# SCH_ESP32-v3_28-11-2025_2025-11-29.net
KiCad netlist of a schematic drawn in EasyEDA
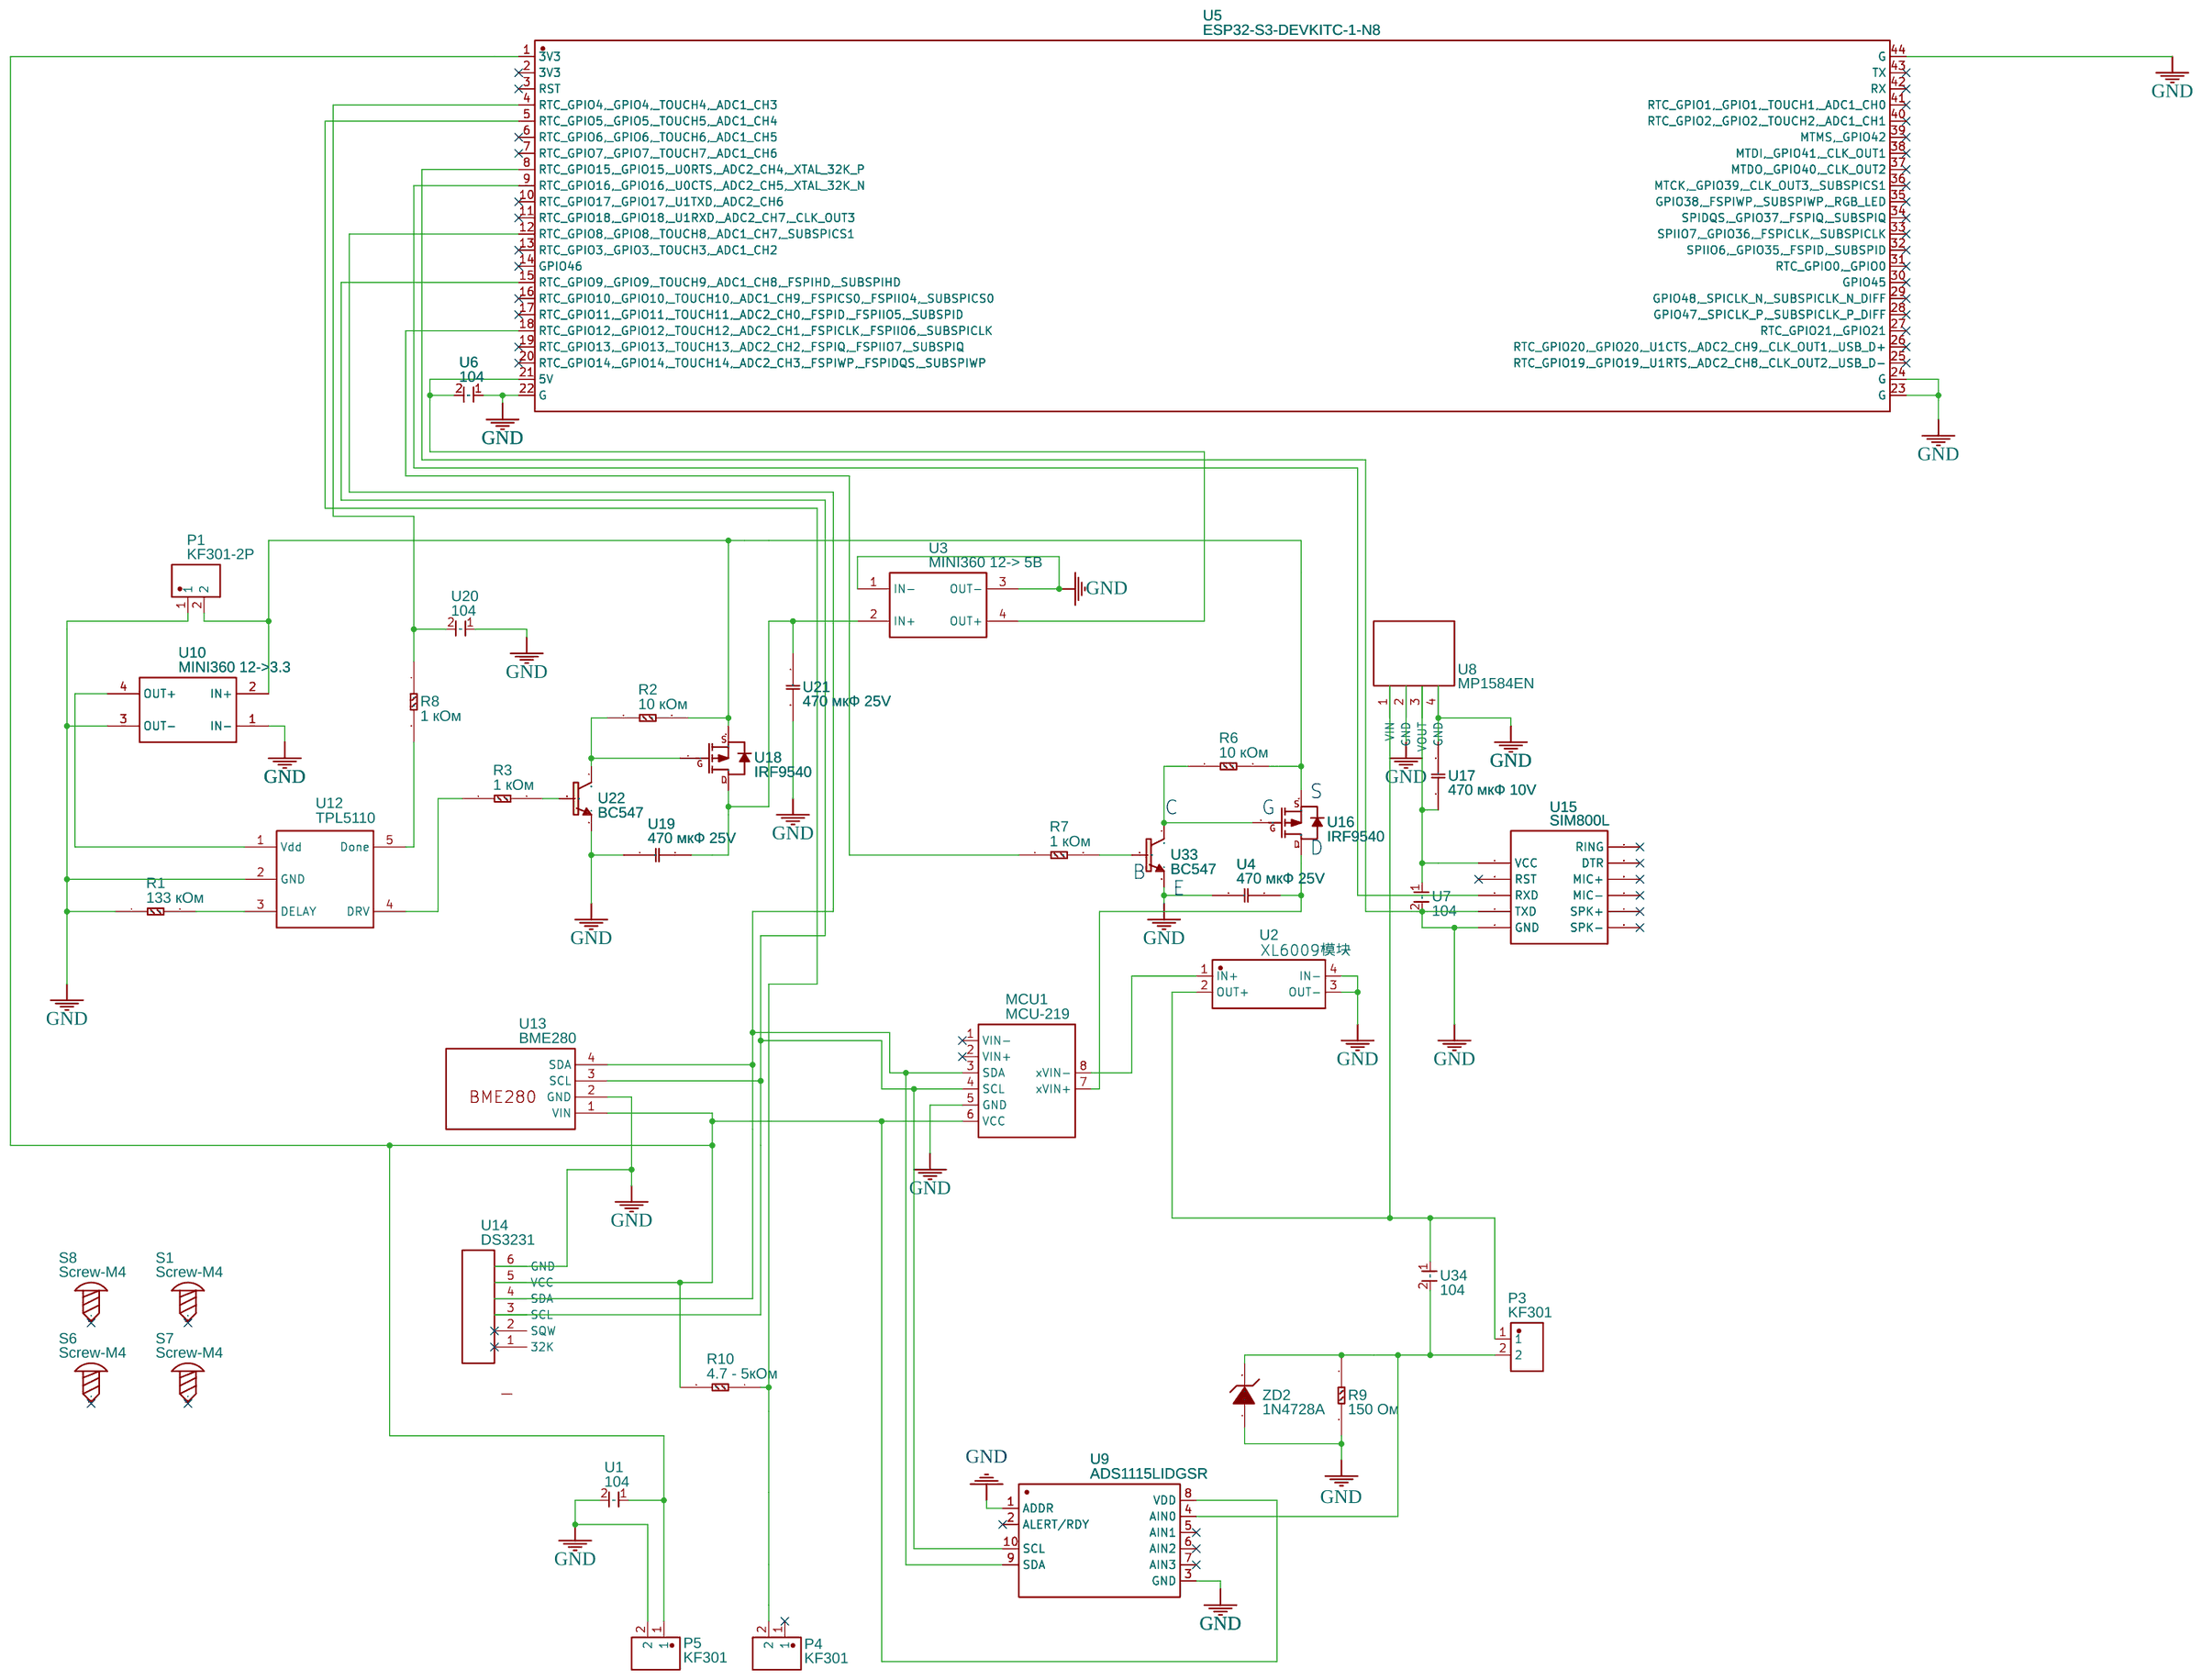
[diagram p0: schematic sheet]

(export (version "E")
  (design (tool "Eeschema 10.0.6"))
  (components
    (comp (ref "MCU1") (value "MCU-219") (libsource (lib "") (part "MCU-219")))
    (comp (ref "P1")
      (value "KF301-2P")
      (fields (field (name "Manufacturer Part") "KF301-2P接线端子"))
      (libsource (lib "") (part "KF301-2P VCC Y GND"))
    )
    (comp (ref "P3")
      (value "KF301")
      (fields (field (name "Manufacturer Part") "KF301-2P接线端子"))
      (libsource (lib "") (part "KF301-2P VCC Y GND_2"))
    )
    (comp (ref "P4")
      (value "KF301")
      (fields (field (name "Manufacturer Part") "KF301-2P接线端子"))
      (libsource (lib "") (part "KF301-2P VCC Y GND_1"))
    )
    (comp (ref "P5")
      (value "KF301")
      (fields (field (name "Manufacturer Part") "KF301-2P接线端子"))
      (libsource (lib "") (part "KF301-2P VCC Y GND_1"))
    )
    (comp (ref "R1") (value "133 кОм") (libsource (lib "") (part "R_")))
    (comp (ref "R2") (value "10 кОм") (libsource (lib "") (part "R_")))
    (comp (ref "R3") (value "1 кОм") (libsource (lib "") (part "R_")))
    (comp (ref "R6") (value "10 кОм") (libsource (lib "") (part "R_")))
    (comp (ref "R7") (value "1 кОм") (libsource (lib "") (part "R_")))
    (comp (ref "R8") (value "1 кОм") (libsource (lib "") (part "R__2")))
    (comp (ref "R9") (value "150 Ом") (libsource (lib "") (part "R__2")))
    (comp (ref "R10") (value "4.7 - 5кОм") (libsource (lib "") (part "R__1")))
    (comp (ref "S1") (value "Screw-M4") (libsource (lib "") (part "Screw-M4")))
    (comp (ref "S6") (value "Screw-M4") (libsource (lib "") (part "Screw-M4")))
    (comp (ref "S7") (value "Screw-M4") (libsource (lib "") (part "Screw-M4")))
    (comp (ref "S8") (value "Screw-M4") (libsource (lib "") (part "Screw-M4")))
    (comp (ref "U1")
      (value "104")
      (fields (field (name "Manufacturer") "Fe"))
      (libsource (lib "") (part "104"))
    )
    (comp (ref "U2")
      (value "XL6009模块")
      (fields (field (name "Manufacturer Part") "xl6009模块"))
      (libsource (lib "") (part "XL6009模块"))
    )
    (comp (ref "U3")
      (value "MINI360 12-> 5В")
      (fields (field (name "Manufacturer Part") "Mini360"))
      (libsource (lib "") (part "MINI360BUCK"))
    )
    (comp (ref "U4") (value "470 мкФ 25V") (libsource (lib "") (part "C__1")))
    (comp (ref "U5")
      (value "ESP32-S3-DEVKITC-1-N8")
      (fields (field (name "Manufacturer") "ESPRESSIF(乐鑫)"))
      (libsource (lib "") (part "ESP32-S3-DEVKITC-1-N8"))
    )
    (comp (ref "U6")
      (value "104")
      (fields (field (name "Manufacturer") "Fe"))
      (libsource (lib "") (part "104"))
    )
    (comp (ref "U7")
      (value "104")
      (fields (field (name "Manufacturer") "Fe"))
      (libsource (lib "") (part "104_1"))
    )
    (comp (ref "U8") (value "MP1584EN") (libsource (lib "") (part "MP1584EN")))
    (comp (ref "U9")
      (value "ADS1115LIDGSR")
      (fields (field (name "Manufacturer") "TI(德州仪器)"))
      (libsource (lib "") (part "ADS1115LIDGSR"))
    )
    (comp (ref "U10")
      (value "MINI360 12->3.3")
      (fields (field (name "Manufacturer Part") "Mini360"))
      (libsource (lib "") (part "MINI360BUCK_1"))
    )
    (comp (ref "U12")
      (value "TPL5110")
      (fields (field (name "Manufacturer Part") "3435"))
      (libsource (lib "") (part "ADAFRUIT TPL5110 BREAKOUT"))
    )
    (comp (ref "U13") (value "BME280") (libsource (lib "") (part "BME280")))
    (comp (ref "U14") (value "DS3231") (libsource (lib "") (part "DS3231 upright")))
    (comp (ref "U15") (value "SIM800L") (libsource (lib "") (part "SIM800L")))
    (comp (ref "U16") (value "IRF9540") (libsource (lib "") (part "IRF9540")))
    (comp (ref "U17") (value "470 мкФ 10V") (libsource (lib "") (part "C_")))
    (comp (ref "U18") (value "IRF9540") (libsource (lib "") (part "IRF9540")))
    (comp (ref "U19") (value "470 мкФ 25V") (libsource (lib "") (part "C__1")))
    (comp (ref "U20")
      (value "104")
      (fields (field (name "Manufacturer") "Fe"))
      (libsource (lib "") (part "104"))
    )
    (comp (ref "U21") (value "470 мкФ 25V") (libsource (lib "") (part "C_")))
    (comp (ref "U22") (value "BC547") (libsource (lib "") (part "BC547")))
    (comp (ref "U33") (value "BC547") (libsource (lib "") (part "BC547")))
    (comp (ref "U34")
      (value "104")
      (fields (field (name "Manufacturer") "Fe"))
      (libsource (lib "") (part "104_1"))
    )
    (comp (ref "ZD2")
      (value "1N4728A")
      (fields (field (name "Manufacturer") "ST(先科)"))
      (libsource (lib "") (part "1N4728A"))
    )
  )
  (nets
    (net (code "1") (name "GND") (class "Default")
      (node (ref "MCU1") (pin "5") (pinfunction "GND_5") (pintype "unspecified"))
      (node (ref "P1") (pin "1") (pinfunction "1_1") (pintype "unspecified"))
      (node (ref "P5") (pin "2") (pinfunction "2_2") (pintype "unspecified"))
      (node (ref "R1") (pin "1") (pinfunction "1_1") (pintype "unspecified"))
      (node (ref "R9") (pin "2") (pinfunction "2_2") (pintype "unspecified"))
      (node (ref "U1") (pin "2") (pinfunction "2_2") (pintype "unspecified"))
      (node (ref "U10") (pin "1") (pinfunction "IN-_1") (pintype "unspecified"))
      (node (ref "U10") (pin "3") (pinfunction "OUT-_3") (pintype "unspecified"))
      (node (ref "U12") (pin "2") (pinfunction "GND_2") (pintype "unspecified"))
      (node (ref "U13") (pin "2") (pinfunction "GND_2") (pintype "unspecified"))
      (node (ref "U14") (pin "6") (pinfunction "GND_6") (pintype "unspecified"))
      (node (ref "U15") (pin "4") (pinfunction "TXD_4") (pintype "unspecified"))
      (node (ref "U15") (pin "5") (pinfunction "GND_5") (pintype "unspecified"))
      (node (ref "U17") (pin "1") (pinfunction "1_1") (pintype "unspecified"))
      (node (ref "U19") (pin "1") (pinfunction "1_1") (pintype "unspecified"))
      (node (ref "U2") (pin "3") (pinfunction "OUT-_3") (pintype "unspecified"))
      (node (ref "U2") (pin "4") (pinfunction "IN-_4") (pintype "unspecified"))
      (node (ref "U20") (pin "1") (pinfunction "1_1") (pintype "unspecified"))
      (node (ref "U21") (pin "2") (pinfunction "2_2") (pintype "unspecified"))
      (node (ref "U22") (pin "3") (pinfunction "E_3") (pintype "unspecified"))
      (node (ref "U3") (pin "1") (pinfunction "IN-_1") (pintype "unspecified"))
      (node (ref "U3") (pin "3") (pinfunction "OUT-_3") (pintype "unspecified"))
      (node (ref "U33") (pin "3") (pinfunction "E_3") (pintype "unspecified"))
      (node (ref "U4") (pin "1") (pinfunction "1_1") (pintype "unspecified"))
      (node (ref "U5") (pin "22") (pinfunction "G_22") (pintype "unspecified"))
      (node (ref "U5") (pin "23") (pinfunction "G_23") (pintype "unspecified"))
      (node (ref "U5") (pin "24") (pinfunction "G_24") (pintype "unspecified"))
      (node (ref "U5") (pin "44") (pinfunction "G_44") (pintype "unspecified"))
      (node (ref "U5") (pin "8") (pinfunction "RTC_GPIO15,_GPIO15,_U0RTS,_ADC2_CH4,_XTAL_32K_P_8") (pintype "unspecified"))
      (node (ref "U6") (pin "1") (pinfunction "1_1") (pintype "unspecified"))
      (node (ref "U7") (pin "2") (pinfunction "2_2") (pintype "unspecified"))
      (node (ref "U8") (pin "2") (pinfunction "GND_2") (pintype "unspecified"))
      (node (ref "U8") (pin "4") (pinfunction "GND_4") (pintype "unspecified"))
      (node (ref "U9") (pin "1") (pinfunction "ADDR_1") (pintype "unspecified"))
      (node (ref "U9") (pin "3") (pinfunction "GND_3") (pintype "unspecified"))
      (node (ref "ZD2") (pin "1") (pinfunction "A_1") (pintype "unspecified"))
    )
    (net (code "2") (name "Net-(MCU1-SCL)") (class "Default")
      (node (ref "MCU1") (pin "4") (pinfunction "SCL_4") (pintype "unspecified"))
      (node (ref "U13") (pin "3") (pinfunction "SCL_3") (pintype "unspecified"))
      (node (ref "U14") (pin "3") (pinfunction "SCL_3") (pintype "unspecified"))
      (node (ref "U5") (pin "15") (pinfunction "RTC_GPIO9,_GPIO9,_TOUCH9,_ADC1_CH8,_FSPIHD,_SUBSPIHD_15") (pintype "unspecified"))
      (node (ref "U9") (pin "10") (pinfunction "SCL_10") (pintype "unspecified"))
    )
    (net (code "3") (name "Net-(MCU1-SDA)") (class "Default")
      (node (ref "MCU1") (pin "3") (pinfunction "SDA_3") (pintype "unspecified"))
      (node (ref "U13") (pin "4") (pinfunction "SDA_4") (pintype "unspecified"))
      (node (ref "U14") (pin "4") (pinfunction "SDA_4") (pintype "unspecified"))
      (node (ref "U5") (pin "12") (pinfunction "RTC_GPIO8,_GPIO8,_TOUCH8,_ADC1_CH7,_SUBSPICS1_12") (pintype "unspecified"))
      (node (ref "U9") (pin "9") (pinfunction "SDA_9") (pintype "unspecified"))
    )
    (net (code "4") (name "Net-(MCU1-VCC)") (class "Default")
      (node (ref "MCU1") (pin "6") (pinfunction "VCC_6") (pintype "unspecified"))
      (node (ref "P5") (pin "1") (pinfunction "1_1") (pintype "unspecified"))
      (node (ref "R10") (pin "2") (pinfunction "2_2") (pintype "unspecified"))
      (node (ref "U1") (pin "1") (pinfunction "1_1") (pintype "unspecified"))
      (node (ref "U13") (pin "1") (pinfunction "VIN_1") (pintype "unspecified"))
      (node (ref "U14") (pin "5") (pinfunction "VCC_5") (pintype "unspecified"))
      (node (ref "U5") (pin "1") (pinfunction "3V3_1") (pintype "unspecified"))
      (node (ref "U9") (pin "8") (pinfunction "VDD_8") (pintype "unspecified"))
    )
    (net (code "5") (name "Net-(MCU1-xVIN+)") (class "Default")
      (node (ref "MCU1") (pin "7") (pinfunction "xVIN+_7") (pintype "unspecified"))
      (node (ref "U16") (pin "2") (pinfunction "D_2") (pintype "unspecified"))
      (node (ref "U4") (pin "2") (pinfunction "2_2") (pintype "unspecified"))
    )
    (net (code "6") (name "Net-(MCU1-xVIN-)") (class "Default")
      (node (ref "MCU1") (pin "8") (pinfunction "xVIN-_8") (pintype "unspecified"))
      (node (ref "U2") (pin "1") (pinfunction "IN+_1") (pintype "unspecified"))
    )
    (net (code "7") (name "Net-(U2-OUT+)") (class "Default")
      (node (ref "P3") (pin "1") (pinfunction "1_1") (pintype "unspecified"))
      (node (ref "U2") (pin "2") (pinfunction "OUT+_2") (pintype "unspecified"))
      (node (ref "U34") (pin "1") (pinfunction "1_1") (pintype "unspecified"))
      (node (ref "U8") (pin "1") (pinfunction "VIN_1") (pintype "unspecified"))
    )
    (net (code "8") (name "Net-(U3-OUT+)") (class "Default")
      (node (ref "U3") (pin "4") (pinfunction "OUT+_4") (pintype "unspecified"))
      (node (ref "U5") (pin "21") (pinfunction "5V_21") (pintype "unspecified"))
      (node (ref "U6") (pin "2") (pinfunction "2_2") (pintype "unspecified"))
    )
    (net (code "9") (name "Net-(U5-RTC_GPIO4,_GPIO4,_TOUCH4,_ADC1_CH3)") (class "Default")
      (node (ref "R8") (pin "1") (pinfunction "1_1") (pintype "unspecified"))
      (node (ref "U20") (pin "2") (pinfunction "2_2") (pintype "unspecified"))
      (node (ref "U5") (pin "4") (pinfunction "RTC_GPIO4,_GPIO4,_TOUCH4,_ADC1_CH3_4") (pintype "unspecified"))
    )
    (net (code "10") (name "Net-(U5-RTC_GPIO5,_GPIO5,_TOUCH5,_ADC1_CH4)") (class "Default")
      (node (ref "P4") (pin "2") (pinfunction "2_2") (pintype "unspecified"))
      (node (ref "R10") (pin "1") (pinfunction "1_1") (pintype "unspecified"))
      (node (ref "U5") (pin "5") (pinfunction "RTC_GPIO5,_GPIO5,_TOUCH5,_ADC1_CH4_5") (pintype "unspecified"))
    )
    (net (code "11") (name "Net-(U5-RTC_GPIO12,_GPIO12,_TOUCH12,_ADC2_CH1,_FSPICLK,_FSPIIO6,_SUBSPICLK)") (class "Default")
      (node (ref "R7") (pin "1") (pinfunction "1_1") (pintype "unspecified"))
      (node (ref "U5") (pin "18") (pinfunction "RTC_GPIO12,_GPIO12,_TOUCH12,_ADC2_CH1,_FSPICLK,_FSPIIO6,_SUBSPICLK_18") (pintype "unspecified"))
    )
    (net (code "12") (name "Net-(U9-AIN0)") (class "Default")
      (node (ref "P3") (pin "2") (pinfunction "2_2") (pintype "unspecified"))
      (node (ref "R9") (pin "1") (pinfunction "1_1") (pintype "unspecified"))
      (node (ref "U34") (pin "2") (pinfunction "2_2") (pintype "unspecified"))
      (node (ref "U9") (pin "4") (pinfunction "AIN0_4") (pintype "unspecified"))
      (node (ref "ZD2") (pin "2") (pinfunction "K_2") (pintype "unspecified"))
    )
    (net (code "13") (name "Net-(U10-IN+)") (class "Default")
      (node (ref "P1") (pin "2") (pinfunction "2_2") (pintype "unspecified"))
      (node (ref "R2") (pin "2") (pinfunction "2_2") (pintype "unspecified"))
      (node (ref "R6") (pin "2") (pinfunction "2_2") (pintype "unspecified"))
      (node (ref "U10") (pin "2") (pinfunction "IN+_2") (pintype "unspecified"))
      (node (ref "U16") (pin "3") (pinfunction "S_3") (pintype "unspecified"))
      (node (ref "U18") (pin "3") (pinfunction "S_3") (pintype "unspecified"))
    )
    (net (code "14") (name "Net-(U10-OUT+)") (class "Default")
      (node (ref "U10") (pin "4") (pinfunction "OUT+_4") (pintype "unspecified"))
      (node (ref "U12") (pin "1") (pinfunction "Vdd_1") (pintype "unspecified"))
    )
    (net (code "15") (name "Net-(U12-DELAY)") (class "Default")
      (node (ref "R1") (pin "2") (pinfunction "2_2") (pintype "unspecified"))
      (node (ref "U12") (pin "3") (pinfunction "DELAY_3") (pintype "unspecified"))
    )
    (net (code "16") (name "Net-(U12-DRV)") (class "Default")
      (node (ref "R3") (pin "1") (pinfunction "1_1") (pintype "unspecified"))
      (node (ref "U12") (pin "4") (pinfunction "DRV_4") (pintype "unspecified"))
    )
    (net (code "17") (name "Net-(U12-Done)") (class "Default")
      (node (ref "R8") (pin "2") (pinfunction "2_2") (pintype "unspecified"))
      (node (ref "U12") (pin "5") (pinfunction "Done_5") (pintype "unspecified"))
    )
    (net (code "18") (name "Net-(U15-RXD)") (class "Default")
      (node (ref "U15") (pin "3") (pinfunction "RXD_3") (pintype "unspecified"))
      (node (ref "U5") (pin "9") (pinfunction "RTC_GPIO16,_GPIO16,_U0CTS,_ADC2_CH5,_XTAL_32K_N_9") (pintype "unspecified"))
    )
    (net (code "19") (name "Net-(U15-VCC)") (class "Default")
      (node (ref "U15") (pin "1") (pinfunction "VCC_1") (pintype "unspecified"))
      (node (ref "U17") (pin "2") (pinfunction "2_2") (pintype "unspecified"))
      (node (ref "U7") (pin "1") (pinfunction "1_1") (pintype "unspecified"))
      (node (ref "U8") (pin "3") (pinfunction "VOUT_3") (pintype "unspecified"))
    )
    (net (code "20") (name "Net-(U16-G)") (class "Default")
      (node (ref "R6") (pin "1") (pinfunction "1_1") (pintype "unspecified"))
      (node (ref "U16") (pin "1") (pinfunction "G_1") (pintype "unspecified"))
      (node (ref "U33") (pin "1") (pinfunction "C_1") (pintype "unspecified"))
    )
    (net (code "21") (name "Net-(U18-D)") (class "Default")
      (node (ref "U18") (pin "2") (pinfunction "D_2") (pintype "unspecified"))
      (node (ref "U19") (pin "2") (pinfunction "2_2") (pintype "unspecified"))
      (node (ref "U21") (pin "1") (pinfunction "1_1") (pintype "unspecified"))
      (node (ref "U3") (pin "2") (pinfunction "IN+_2") (pintype "unspecified"))
    )
    (net (code "22") (name "Net-(U18-G)") (class "Default")
      (node (ref "R2") (pin "1") (pinfunction "1_1") (pintype "unspecified"))
      (node (ref "U18") (pin "1") (pinfunction "G_1") (pintype "unspecified"))
      (node (ref "U22") (pin "1") (pinfunction "C_1") (pintype "unspecified"))
    )
    (net (code "23") (name "Net-(U22-B)") (class "Default")
      (node (ref "R3") (pin "2") (pinfunction "2_2") (pintype "unspecified"))
      (node (ref "U22") (pin "2") (pinfunction "B_2") (pintype "unspecified"))
    )
    (net (code "24") (name "Net-(U33-B)") (class "Default")
      (node (ref "R7") (pin "2") (pinfunction "2_2") (pintype "unspecified"))
      (node (ref "U33") (pin "2") (pinfunction "B_2") (pintype "unspecified"))
    )
    (net (code "25") (name "unconnected-(MCU1-VIN+-Pad2)") (class "Default")
      (node (ref "MCU1") (pin "2") (pinfunction "VIN+_2") (pintype "unspecified+no_connect"))
    )
    (net (code "26") (name "unconnected-(MCU1-VIN--Pad1)") (class "Default")
      (node (ref "MCU1") (pin "1") (pinfunction "VIN-_1") (pintype "unspecified+no_connect"))
    )
    (net (code "27") (name "unconnected-(P4-Pad1)") (class "Default")
      (node (ref "P4") (pin "1") (pinfunction "1_1") (pintype "unspecified+no_connect"))
    )
    (net (code "28") (name "unconnected-(S1-Pad1)") (class "Default")
      (node (ref "S1") (pin "1") (pinfunction "1_1") (pintype "unspecified+no_connect"))
    )
    (net (code "29") (name "unconnected-(S6-Pad1)") (class "Default")
      (node (ref "S6") (pin "1") (pinfunction "1_1") (pintype "unspecified+no_connect"))
    )
    (net (code "30") (name "unconnected-(S7-Pad1)") (class "Default")
      (node (ref "S7") (pin "1") (pinfunction "1_1") (pintype "unspecified+no_connect"))
    )
    (net (code "31") (name "unconnected-(S8-Pad1)") (class "Default")
      (node (ref "S8") (pin "1") (pinfunction "1_1") (pintype "unspecified+no_connect"))
    )
    (net (code "32") (name "unconnected-(U5-3V3-Pad2)") (class "Default")
      (node (ref "U5") (pin "2") (pinfunction "3V3_2") (pintype "unspecified+no_connect"))
    )
    (net (code "33") (name "unconnected-(U5-GPIO38,_FSPIWP,_SUBSPIWP,_RGB_LED-Pad35)") (class "Default")
      (node (ref "U5") (pin "35") (pinfunction "GPIO38,_FSPIWP,_SUBSPIWP,_RGB_LED_35") (pintype "unspecified+no_connect"))
    )
    (net (code "34") (name "unconnected-(U5-GPIO45-Pad30)") (class "Default")
      (node (ref "U5") (pin "30") (pinfunction "GPIO45_30") (pintype "unspecified+no_connect"))
    )
    (net (code "35") (name "unconnected-(U5-GPIO46-Pad14)") (class "Default")
      (node (ref "U5") (pin "14") (pinfunction "GPIO46_14") (pintype "unspecified+no_connect"))
    )
    (net (code "36") (name "unconnected-(U5-GPIO47,_SPICLK_P,_SUBSPICLK_P_DIFF-Pad28)") (class "Default")
      (node (ref "U5") (pin "28") (pinfunction "GPIO47,_SPICLK_P,_SUBSPICLK_P_DIFF_28") (pintype "unspecified+no_connect"))
    )
    (net (code "37") (name "unconnected-(U5-GPIO48,_SPICLK_N,_SUBSPICLK_N_DIFF-Pad29)") (class "Default")
      (node (ref "U5") (pin "29") (pinfunction "GPIO48,_SPICLK_N,_SUBSPICLK_N_DIFF_29") (pintype "unspecified+no_connect"))
    )
    (net (code "38") (name "unconnected-(U5-MTCK,_GPIO39,_CLK_OUT3,_SUBSPICS1-Pad36)") (class "Default")
      (node (ref "U5") (pin "36") (pinfunction "MTCK,_GPIO39,_CLK_OUT3,_SUBSPICS1_36") (pintype "unspecified+no_connect"))
    )
    (net (code "39") (name "unconnected-(U5-MTDI,_GPIO41,_CLK_OUT1-Pad38)") (class "Default")
      (node (ref "U5") (pin "38") (pinfunction "MTDI,_GPIO41,_CLK_OUT1_38") (pintype "unspecified+no_connect"))
    )
    (net (code "40") (name "unconnected-(U5-MTDO,_GPIO40,_CLK_OUT2-Pad37)") (class "Default")
      (node (ref "U5") (pin "37") (pinfunction "MTDO,_GPIO40,_CLK_OUT2_37") (pintype "unspecified+no_connect"))
    )
    (net (code "41") (name "unconnected-(U5-MTMS,_GPIO42-Pad39)") (class "Default")
      (node (ref "U5") (pin "39") (pinfunction "MTMS,_GPIO42_39") (pintype "unspecified+no_connect"))
    )
    (net (code "42") (name "unconnected-(U5-RST-Pad3)") (class "Default")
      (node (ref "U5") (pin "3") (pinfunction "RST_3") (pintype "unspecified+no_connect"))
    )
    (net (code "43") (name "unconnected-(U5-RTC_GPIO0,_GPIO0-Pad31)") (class "Default")
      (node (ref "U5") (pin "31") (pinfunction "RTC_GPIO0,_GPIO0_31") (pintype "unspecified+no_connect"))
    )
    (net (code "44") (name "unconnected-(U5-RTC_GPIO1,_GPIO1,_TOUCH1,_ADC1_CH0-Pad41)") (class "Default")
      (node (ref "U5") (pin "41") (pinfunction "RTC_GPIO1,_GPIO1,_TOUCH1,_ADC1_CH0_41") (pintype "unspecified+no_connect"))
    )
    (net (code "45") (name "unconnected-(U5-RTC_GPIO2,_GPIO2,_TOUCH2,_ADC1_CH1-Pad40)") (class "Default")
      (node (ref "U5") (pin "40") (pinfunction "RTC_GPIO2,_GPIO2,_TOUCH2,_ADC1_CH1_40") (pintype "unspecified+no_connect"))
    )
    (net (code "46") (name "unconnected-(U5-RTC_GPIO3,_GPIO3,_TOUCH3,_ADC1_CH2-Pad13)") (class "Default")
      (node (ref "U5") (pin "13") (pinfunction "RTC_GPIO3,_GPIO3,_TOUCH3,_ADC1_CH2_13") (pintype "unspecified+no_connect"))
    )
    (net (code "47") (name "unconnected-(U5-RTC_GPIO6,_GPIO6,_TOUCH6,_ADC1_CH5-Pad6)") (class "Default")
      (node (ref "U5") (pin "6") (pinfunction "RTC_GPIO6,_GPIO6,_TOUCH6,_ADC1_CH5_6") (pintype "unspecified+no_connect"))
    )
    (net (code "48") (name "unconnected-(U5-RTC_GPIO7,_GPIO7,_TOUCH7,_ADC1_CH6-Pad7)") (class "Default")
      (node (ref "U5") (pin "7") (pinfunction "RTC_GPIO7,_GPIO7,_TOUCH7,_ADC1_CH6_7") (pintype "unspecified+no_connect"))
    )
    (net (code "49") (name "unconnected-(U5-RTC_GPIO10,_GPIO10,_TOUCH10,_ADC1_CH9,_FSPICS0,_FSPIIO4,_SUBSPICS0-Pad16)") (class "Default")
      (node (ref "U5") (pin "16") (pinfunction "RTC_GPIO10,_GPIO10,_TOUCH10,_ADC1_CH9,_FSPICS0,_FSPIIO4,_SUBSPICS0_16") (pintype "unspecified+no_connect"))
    )
    (net (code "50") (name "unconnected-(U5-RTC_GPIO11,_GPIO11,_TOUCH11,_ADC2_CH0,_FSPID,_FSPIIO5,_SUBSPID-Pad17)") (class "Default")
      (node (ref "U5") (pin "17") (pinfunction "RTC_GPIO11,_GPIO11,_TOUCH11,_ADC2_CH0,_FSPID,_FSPIIO5,_SUBSPID_17") (pintype "unspecified+no_connect"))
    )
    (net (code "51") (name "unconnected-(U5-RTC_GPIO13,_GPIO13,_TOUCH13,_ADC2_CH2,_FSPIQ,_FSPIIO7,_SUBSPIQ-Pad19)") (class "Default")
      (node (ref "U5") (pin "19") (pinfunction "RTC_GPIO13,_GPIO13,_TOUCH13,_ADC2_CH2,_FSPIQ,_FSPIIO7,_SUBSPIQ_19") (pintype "unspecified+no_connect"))
    )
    (net (code "52") (name "unconnected-(U5-RTC_GPIO14,_GPIO14,_TOUCH14,_ADC2_CH3,_FSPIWP,_FSPIDQS,_SUBSPIWP-Pad20)") (class "Default")
      (node (ref "U5") (pin "20") (pinfunction "RTC_GPIO14,_GPIO14,_TOUCH14,_ADC2_CH3,_FSPIWP,_FSPIDQS,_SUBSPIWP_20") (pintype "unspecified+no_connect"))
    )
    (net (code "53") (name "unconnected-(U5-RTC_GPIO17,_GPIO17,_U1TXD,_ADC2_CH6-Pad10)") (class "Default")
      (node (ref "U5") (pin "10") (pinfunction "RTC_GPIO17,_GPIO17,_U1TXD,_ADC2_CH6_10") (pintype "unspecified+no_connect"))
    )
    (net (code "54") (name "unconnected-(U5-RTC_GPIO18,_GPIO18,_U1RXD,_ADC2_CH7,_CLK_OUT3-Pad11)") (class "Default")
      (node (ref "U5") (pin "11") (pinfunction "RTC_GPIO18,_GPIO18,_U1RXD,_ADC2_CH7,_CLK_OUT3_11") (pintype "unspecified+no_connect"))
    )
    (net (code "55") (name "unconnected-(U5-RTC_GPIO19,_GPIO19,_U1RTS,_ADC2_CH8,_CLK_OUT2,_USB_D--Pad25)") (class "Default")
      (node (ref "U5") (pin "25") (pinfunction "RTC_GPIO19,_GPIO19,_U1RTS,_ADC2_CH8,_CLK_OUT2,_USB_D-_25") (pintype "unspecified+no_connect"))
    )
    (net (code "56") (name "unconnected-(U5-RTC_GPIO20,_GPIO20,_U1CTS,_ADC2_CH9,_CLK_OUT1,_USB_D+-Pad26)") (class "Default")
      (node (ref "U5") (pin "26") (pinfunction "RTC_GPIO20,_GPIO20,_U1CTS,_ADC2_CH9,_CLK_OUT1,_USB_D+_26") (pintype "unspecified+no_connect"))
    )
    (net (code "57") (name "unconnected-(U5-RTC_GPIO21,_GPIO21-Pad27)") (class "Default")
      (node (ref "U5") (pin "27") (pinfunction "RTC_GPIO21,_GPIO21_27") (pintype "unspecified+no_connect"))
    )
    (net (code "58") (name "unconnected-(U5-RX-Pad42)") (class "Default")
      (node (ref "U5") (pin "42") (pinfunction "RX_42") (pintype "unspecified+no_connect"))
    )
    (net (code "59") (name "unconnected-(U5-SPIDQS,_GPIO37,_FSPIQ,_SUBSPIQ-Pad34)") (class "Default")
      (node (ref "U5") (pin "34") (pinfunction "SPIDQS,_GPIO37,_FSPIQ,_SUBSPIQ_34") (pintype "unspecified+no_connect"))
    )
    (net (code "60") (name "unconnected-(U5-SPIIO6,_GPIO35,_FSPID,_SUBSPID-Pad32)") (class "Default")
      (node (ref "U5") (pin "32") (pinfunction "SPIIO6,_GPIO35,_FSPID,_SUBSPID_32") (pintype "unspecified+no_connect"))
    )
    (net (code "61") (name "unconnected-(U5-SPIIO7,_GPIO36,_FSPICLK,_SUBSPICLK-Pad33)") (class "Default")
      (node (ref "U5") (pin "33") (pinfunction "SPIIO7,_GPIO36,_FSPICLK,_SUBSPICLK_33") (pintype "unspecified+no_connect"))
    )
    (net (code "62") (name "unconnected-(U5-TX-Pad43)") (class "Default")
      (node (ref "U5") (pin "43") (pinfunction "TX_43") (pintype "unspecified+no_connect"))
    )
    (net (code "63") (name "unconnected-(U9-AIN1-Pad5)") (class "Default")
      (node (ref "U9") (pin "5") (pinfunction "AIN1_5") (pintype "unspecified+no_connect"))
    )
    (net (code "64") (name "unconnected-(U9-AIN2-Pad6)") (class "Default")
      (node (ref "U9") (pin "6") (pinfunction "AIN2_6") (pintype "unspecified+no_connect"))
    )
    (net (code "65") (name "unconnected-(U9-AIN3-Pad7)") (class "Default")
      (node (ref "U9") (pin "7") (pinfunction "AIN3_7") (pintype "unspecified+no_connect"))
    )
    (net (code "66") (name "unconnected-(U9-ALERT{slash}RDY-Pad2)") (class "Default")
      (node (ref "U9") (pin "2") (pinfunction "ALERT/RDY_2") (pintype "unspecified+no_connect"))
    )
    (net (code "67") (name "unconnected-(U14-32K-Pad1)") (class "Default")
      (node (ref "U14") (pin "1") (pinfunction "32K_1") (pintype "unspecified+no_connect"))
    )
    (net (code "68") (name "unconnected-(U14-SQW-Pad2)") (class "Default")
      (node (ref "U14") (pin "2") (pinfunction "SQW_2") (pintype "unspecified+no_connect"))
    )
    (net (code "69") (name "unconnected-(U15-DTR-Pad10)") (class "Default")
      (node (ref "U15") (pin "10") (pinfunction "DTR_10") (pintype "unspecified+no_connect"))
    )
    (net (code "70") (name "unconnected-(U15-MIC+-Pad9)") (class "Default")
      (node (ref "U15") (pin "9") (pinfunction "MIC+_9") (pintype "unspecified+no_connect"))
    )
    (net (code "71") (name "unconnected-(U15-MIC--Pad8)") (class "Default")
      (node (ref "U15") (pin "8") (pinfunction "MIC-_8") (pintype "unspecified+no_connect"))
    )
    (net (code "72") (name "unconnected-(U15-RING-Pad11)") (class "Default")
      (node (ref "U15") (pin "11") (pinfunction "RING_11") (pintype "unspecified+no_connect"))
    )
    (net (code "73") (name "unconnected-(U15-RST-Pad2)") (class "Default")
      (node (ref "U15") (pin "2") (pinfunction "RST_2") (pintype "unspecified+no_connect"))
    )
    (net (code "74") (name "unconnected-(U15-SPK+-Pad7)") (class "Default")
      (node (ref "U15") (pin "7") (pinfunction "SPK+_7") (pintype "unspecified+no_connect"))
    )
    (net (code "75") (name "unconnected-(U15-SPK--Pad6)") (class "Default")
      (node (ref "U15") (pin "6") (pinfunction "SPK-_6") (pintype "unspecified+no_connect"))
    )
  )
)
